# analog_inputs_blk.net
KiCad netlist of a schematic drawn in Altium Designer
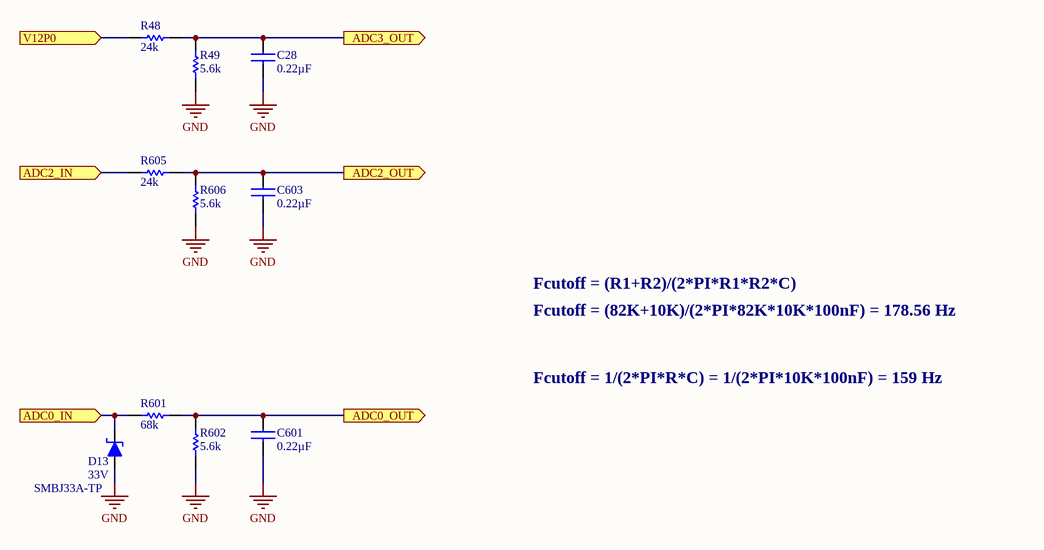
[diagram p0: analog_inputs_blk.SchDoc]

(export (version "E")
  (design (tool "Eeschema 10.0.6"))
  (components
    (comp (ref "C28")
      (value "0.22µF")
      (footprint "C0603")
      (description "CAP CER 0.22UF 50V X7R 0603")
      (fields (field (name "MPN") "GCM188R71H224KA64D"))
      (libsource (lib "Capacitor") (part "GCM188R71H224KA64D"))
    )
    (comp (ref "C601")
      (value "0.22µF")
      (footprint "C0603")
      (description "CAP CER 0.22UF 50V X7R 0603")
      (fields (field (name "MPN") "GCM188R71H224KA64D"))
      (libsource (lib "WiLamp") (part "GCM188R71H224KA64D"))
    )
    (comp (ref "C603")
      (value "0.22µF")
      (footprint "C0603")
      (description "CAP CER 0.22UF 50V X7R 0603")
      (fields (field (name "MPN") "GCM188R71H224KA64D"))
      (libsource (lib "Capacitor") (part "GCM188R71H224KA64D"))
    )
    (comp (ref "D13")
      (value "SMBJ33A-TP")
      (footprint "DO-214AA, SMB")
      (description "TVS DIODE 33VWM 53.3VC SMB")
      (fields (field (name "RATING") "33V") (field (name "MPN") "SMBJ33A-TP"))
      (libsource (lib "Diode") (part "SMBJ33A-TP"))
    )
    (comp (ref "R48")
      (value "24k")
      (footprint "R0603")
      (description "RES 24K OHM 0.1% 1/8W 0603")
      (fields (field (name "MPN") "TNPW060324K0BEEA"))
      (libsource (lib "Res") (part "TNPW060324K0BEEA"))
    )
    (comp (ref "R49")
      (value "5.6k")
      (footprint "R0603")
      (description "RES SMD 5.6K OHM 0.1% 1/10W 0603")
      (fields (field (name "MPN") "ERA-3AEB562V"))
      (libsource (lib "Res") (part "ERA-3AEB562V"))
    )
    (comp (ref "R601")
      (value "68k")
      (footprint "R0603")
      (description "RES SMD 68K OHM 0.1% 1/10W 0603")
      (fields (field (name "MPN") "ERA-3AEB683V"))
      (libsource (lib "Res") (part "ERA-3AEB683V"))
    )
    (comp (ref "R602")
      (value "5.6k")
      (footprint "R0603")
      (description "RES SMD 5.6K OHM 0.1% 1/10W 0603")
      (fields (field (name "MPN") "ERA-3AEB562V"))
      (libsource (lib "Res") (part "ERA-3AEB562V"))
    )
    (comp (ref "R605")
      (value "24k")
      (footprint "R0603")
      (description "RES SMD 24K OHM 0.1% 1/8W 0603")
      (fields (field (name "MPN") "TNPW060324K0BEEA"))
      (libsource (lib "Res") (part "TNPW060324K0BEEA"))
    )
    (comp (ref "R606")
      (value "5.6k")
      (footprint "R0603")
      (description "RES SMD 5.6K OHM 0.1% 1/10W 0603")
      (fields (field (name "MPN") "ERA-3AEB562V"))
      (libsource (lib "Res") (part "ERA-3AEB562V"))
    )
  )
  (nets
    (net (code "1") (name "/ADC0_IN") (class "Default")
      (node (ref "D13") (pin "1") (pinfunction "K_1") (pintype "passive"))
      (node (ref "R601") (pin "1") (pinfunction "1_1") (pintype "passive"))
    )
    (net (code "2") (name "/ADC0_OUT") (class "Default")
      (node (ref "C601") (pin "1") (pinfunction "1_1") (pintype "passive"))
      (node (ref "R601") (pin "2") (pinfunction "2_2") (pintype "passive"))
      (node (ref "R602") (pin "2") (pinfunction "2_2") (pintype "passive"))
    )
    (net (code "3") (name "/ADC2_IN") (class "Default")
      (node (ref "R605") (pin "1") (pinfunction "1_1") (pintype "passive"))
    )
    (net (code "4") (name "/ADC2_OUT") (class "Default")
      (node (ref "C603") (pin "1") (pinfunction "1_1") (pintype "passive"))
      (node (ref "R605") (pin "2") (pinfunction "2_2") (pintype "passive"))
      (node (ref "R606") (pin "2") (pinfunction "2_2") (pintype "passive"))
    )
    (net (code "5") (name "/ADC3_OUT") (class "Default")
      (node (ref "C28") (pin "1") (pinfunction "1_1") (pintype "passive"))
      (node (ref "R48") (pin "2") (pinfunction "2_2") (pintype "passive"))
      (node (ref "R49") (pin "2") (pinfunction "2_2") (pintype "passive"))
    )
    (net (code "6") (name "/V12P0") (class "Default")
      (node (ref "R48") (pin "1") (pinfunction "1_1") (pintype "passive"))
    )
    (net (code "7") (name "GND") (class "Default")
      (node (ref "C28") (pin "2") (pinfunction "2_2") (pintype "passive"))
      (node (ref "C601") (pin "2") (pinfunction "2_2") (pintype "passive"))
      (node (ref "C603") (pin "2") (pinfunction "2_2") (pintype "passive"))
      (node (ref "D13") (pin "2") (pinfunction "A_2") (pintype "passive"))
      (node (ref "R49") (pin "1") (pinfunction "1_1") (pintype "passive"))
      (node (ref "R602") (pin "1") (pinfunction "1_1") (pintype "passive"))
      (node (ref "R606") (pin "1") (pinfunction "1_1") (pintype "passive"))
    )
  )
)
